# SENSOR_SCH.net
KiCad netlist of a schematic drawn in Altium Designer
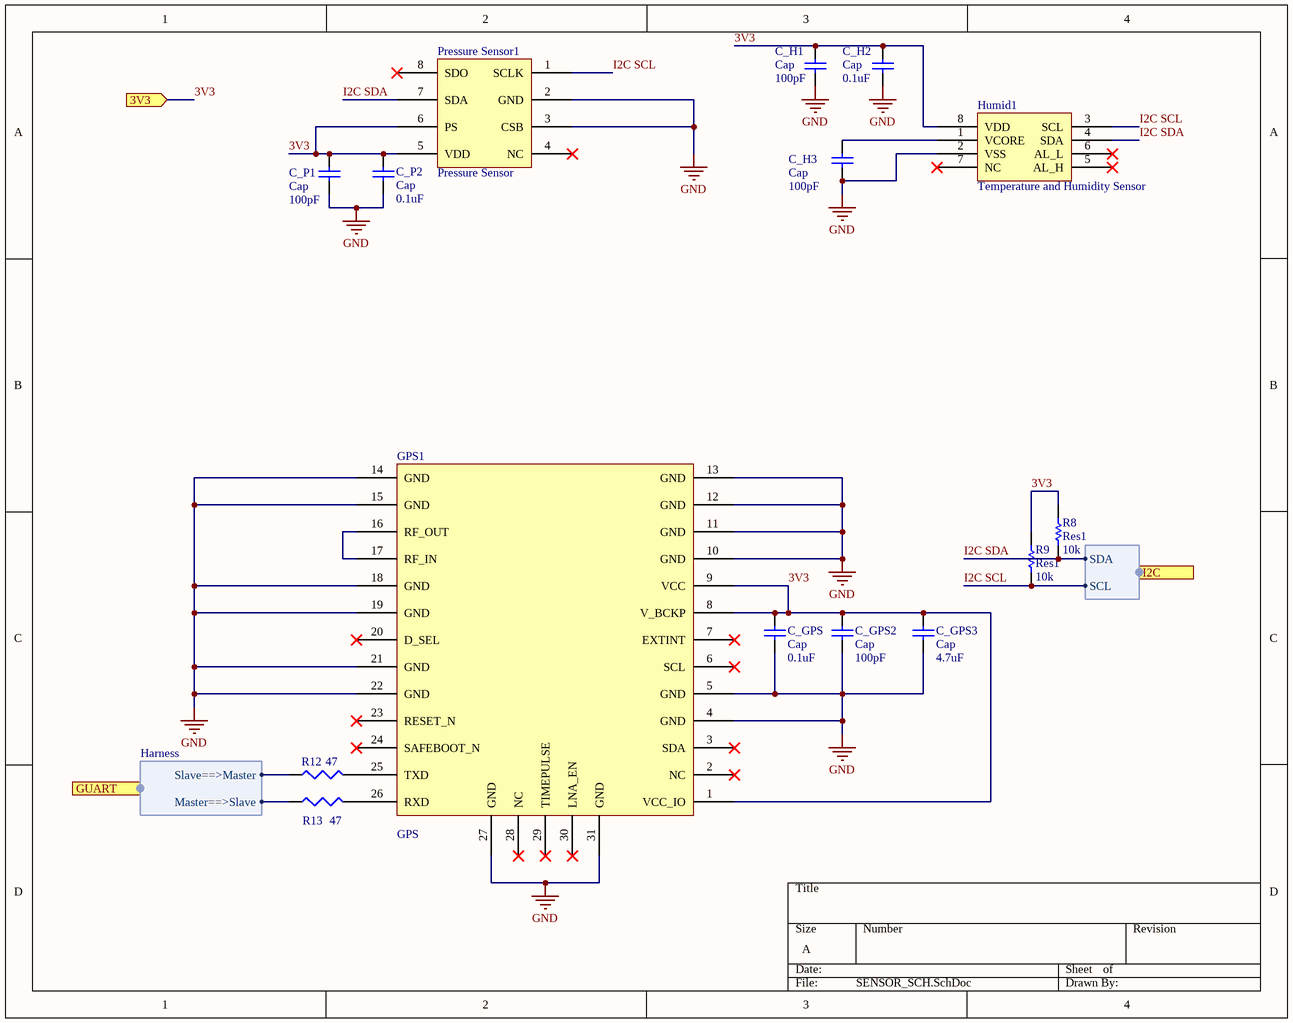
[diagram p0: SENSOR_SCH.SchDoc]

(export (version "E")
  (design (tool "Eeschema 10.0.6"))
  (components
    (comp (ref "C_GPS")
      (value "Cap")
      (footprint "1608[0603]")
      (description "Capacitor")
      (fields (field (name "ALTIUM_VALUE") "0.1uF") (field (name "PUBLISHER") "Altium Limited"))
      (libsource (lib "Miscellaneous Devices") (part "Cap"))
    )
    (comp (ref "C_GPS2")
      (value "Cap")
      (footprint "1608[0603]")
      (description "Capacitor")
      (fields (field (name "ALTIUM_VALUE") "100pF") (field (name "PUBLISHER") "Altium Limited"))
      (libsource (lib "Miscellaneous Devices") (part "Cap"))
    )
    (comp (ref "C_GPS3")
      (value "Cap")
      (footprint "1608[0603]")
      (description "Capacitor")
      (fields (field (name "ALTIUM_VALUE") "4.7uF") (field (name "PUBLISHER") "Altium Limited"))
      (libsource (lib "Miscellaneous Devices") (part "Cap"))
    )
    (comp (ref "C_H1")
      (value "Cap")
      (footprint "1608[0603]")
      (description "Capacitor")
      (fields (field (name "ALTIUM_VALUE") "100pF") (field (name "PUBLISHER") "Altium Limited"))
      (libsource (lib "Miscellaneous Devices") (part "Cap"))
    )
    (comp (ref "C_H2")
      (value "Cap")
      (footprint "1608[0603]")
      (description "Capacitor")
      (fields (field (name "ALTIUM_VALUE") "0.1uF") (field (name "PUBLISHER") "Altium Limited"))
      (libsource (lib "Miscellaneous Devices") (part "Cap"))
    )
    (comp (ref "C_H3")
      (value "Cap")
      (footprint "1608[0603]")
      (description "Capacitor")
      (fields (field (name "ALTIUM_VALUE") "100pF") (field (name "PUBLISHER") "Altium Limited"))
      (libsource (lib "Miscellaneous Devices") (part "Cap"))
    )
    (comp (ref "C_P1")
      (value "Cap")
      (footprint "1608[0603]")
      (description "Capacitor")
      (fields (field (name "ALTIUM_VALUE") "100pF") (field (name "PUBLISHER") "Altium Limited"))
      (libsource (lib "Miscellaneous Devices") (part "Cap"))
    )
    (comp (ref "C_P2")
      (value "Cap")
      (footprint "1608[0603]")
      (description "Capacitor")
      (fields (field (name "ALTIUM_VALUE") "0.1uF") (field (name "PUBLISHER") "Altium Limited"))
      (libsource (lib "Miscellaneous Devices") (part "Cap"))
    )
    (comp (ref "GPS1")
      (value "GPS")
      (footprint "CAM M8C GPS")
      (description "CAM M8C")
      (libsource (lib "ATACS_SCH_LIB") (part "GPS"))
    )
    (comp (ref "Humid1")
      (value "Temperature and Humidity Sensor")
      (footprint "Humidity Sensor")
      (description "HIH6030-021-001")
      (libsource (lib "ATACS_SCH_LIB") (part "Temperature and Humidity Sensor"))
    )
    (comp (ref "Pressure Sensor1")
      (value "Pressure Sensor")
      (footprint "Pressure Sensor")
      (description "MS580301BA01-00")
      (libsource (lib "ATACS_SCH_LIB") (part "Pressure Sensor"))
    )
    (comp (ref "R8")
      (value "Res1")
      (footprint "J1-0603")
      (description "Resistor")
      (fields (field (name "ALTIUM_VALUE") "10k") (field (name "PUBLISHER") "Altium Limited"))
      (libsource (lib "Miscellaneous Devices") (part "Res1"))
    )
    (comp (ref "R9")
      (value "Res1")
      (footprint "J1-0603")
      (description "Resistor")
      (fields (field (name "ALTIUM_VALUE") "10k") (field (name "PUBLISHER") "Altium Limited"))
      (libsource (lib "Miscellaneous Devices") (part "Res1"))
    )
    (comp (ref "R12")
      (value "47")
      (footprint "J1-0603")
      (description "Resistor")
      (fields (field (name "Comment") "Res3") (field (name "PUBLISHER") "Altium Limited"))
      (libsource (lib "Miscellaneous Devices") (part "Res3"))
    )
    (comp (ref "R13")
      (value "47")
      (footprint "J1-0603")
      (description "Resistor")
      (fields (field (name "Comment") "Res3") (field (name "PUBLISHER") "Altium Limited"))
      (libsource (lib "Miscellaneous Devices") (part "Res3"))
    )
  )
  (nets
    (net (code "3") (name "/3V3") (class "Default")
      (node (ref "C_GPS") (pin "2") (pinfunction "2_2") (pintype "passive"))
      (node (ref "C_GPS2") (pin "2") (pinfunction "2_2") (pintype "passive"))
      (node (ref "C_GPS3") (pin "2") (pinfunction "2_2") (pintype "passive"))
      (node (ref "C_H1") (pin "2") (pinfunction "2_2") (pintype "passive"))
      (node (ref "C_H2") (pin "2") (pinfunction "2_2") (pintype "passive"))
      (node (ref "C_P1") (pin "2") (pinfunction "2_2") (pintype "passive"))
      (node (ref "C_P2") (pin "2") (pinfunction "2_2") (pintype "passive"))
      (node (ref "GPS1") (pin "1") (pinfunction "VCC_IO_1") (pintype "passive"))
      (node (ref "GPS1") (pin "8") (pinfunction "V_BCKP_8") (pintype "passive"))
      (node (ref "GPS1") (pin "9") (pinfunction "VCC_9") (pintype "passive"))
      (node (ref "Humid1") (pin "8") (pinfunction "VDD_8") (pintype "passive"))
      (node (ref "Pressure Sensor1") (pin "5") (pinfunction "VDD_5") (pintype "passive"))
      (node (ref "Pressure Sensor1") (pin "6") (pinfunction "PS_6") (pintype "passive"))
      (node (ref "R8") (pin "2") (pinfunction "2_2") (pintype "passive"))
      (node (ref "R9") (pin "2") (pinfunction "2_2") (pintype "passive"))
    )
    (net (code "4") (name "/I2C SCL") (class "Default")
      (node (ref "Humid1") (pin "3") (pinfunction "SCL_3") (pintype "passive"))
      (node (ref "Pressure Sensor1") (pin "1") (pinfunction "SCLK_1") (pintype "passive"))
      (node (ref "R9") (pin "1") (pinfunction "1_1") (pintype "passive"))
    )
    (net (code "5") (name "/I2C SDA") (class "Default")
      (node (ref "Humid1") (pin "4") (pinfunction "SDA_4") (pintype "passive"))
      (node (ref "Pressure Sensor1") (pin "7") (pinfunction "SDA_7") (pintype "passive"))
      (node (ref "R8") (pin "1") (pinfunction "1_1") (pintype "passive"))
    )
    (net (code "6") (name "/Master==>Slave") (class "Default")
      (node (ref "R13") (pin "1") (pinfunction "1_1") (pintype "passive"))
    )
    (net (code "7") (name "/Slave==>Master") (class "Default")
      (node (ref "R12") (pin "1") (pinfunction "1_1") (pintype "passive"))
    )
    (net (code "10") (name "GND") (class "Default")
      (node (ref "C_GPS") (pin "1") (pinfunction "1_1") (pintype "passive"))
      (node (ref "C_GPS2") (pin "1") (pinfunction "1_1") (pintype "passive"))
      (node (ref "C_GPS3") (pin "1") (pinfunction "1_1") (pintype "passive"))
      (node (ref "C_H1") (pin "1") (pinfunction "1_1") (pintype "passive"))
      (node (ref "C_H2") (pin "1") (pinfunction "1_1") (pintype "passive"))
      (node (ref "C_H3") (pin "1") (pinfunction "1_1") (pintype "passive"))
      (node (ref "C_P1") (pin "1") (pinfunction "1_1") (pintype "passive"))
      (node (ref "C_P2") (pin "1") (pinfunction "1_1") (pintype "passive"))
      (node (ref "GPS1") (pin "10") (pinfunction "GND_10") (pintype "passive"))
      (node (ref "GPS1") (pin "11") (pinfunction "GND_11") (pintype "passive"))
      (node (ref "GPS1") (pin "12") (pinfunction "GND_12") (pintype "passive"))
      (node (ref "GPS1") (pin "13") (pinfunction "GND_13") (pintype "passive"))
      (node (ref "GPS1") (pin "14") (pinfunction "GND_14") (pintype "passive"))
      (node (ref "GPS1") (pin "15") (pinfunction "GND_15") (pintype "passive"))
      (node (ref "GPS1") (pin "18") (pinfunction "GND_18") (pintype "passive"))
      (node (ref "GPS1") (pin "19") (pinfunction "GND_19") (pintype "passive"))
      (node (ref "GPS1") (pin "21") (pinfunction "GND_21") (pintype "passive"))
      (node (ref "GPS1") (pin "22") (pinfunction "GND_22") (pintype "passive"))
      (node (ref "GPS1") (pin "27") (pinfunction "GND_27") (pintype "passive"))
      (node (ref "GPS1") (pin "31") (pinfunction "GND_31") (pintype "passive"))
      (node (ref "GPS1") (pin "4") (pinfunction "GND_4") (pintype "passive"))
      (node (ref "GPS1") (pin "5") (pinfunction "GND_5") (pintype "passive"))
      (node (ref "Humid1") (pin "2") (pinfunction "VSS_2") (pintype "passive"))
      (node (ref "Pressure Sensor1") (pin "2") (pinfunction "GND_2") (pintype "passive"))
      (node (ref "Pressure Sensor1") (pin "3") (pinfunction "CSB_3") (pintype "passive"))
    )
    (net (code "11") (name "Net-(GPS1-RF_IN)") (class "Default")
      (node (ref "GPS1") (pin "16") (pinfunction "RF_OUT_16") (pintype "passive"))
      (node (ref "GPS1") (pin "17") (pinfunction "RF_IN_17") (pintype "passive"))
    )
    (net (code "12") (name "Net-(GPS1-RXD)") (class "Default")
      (node (ref "GPS1") (pin "26") (pinfunction "RXD_26") (pintype "passive"))
      (node (ref "R13") (pin "2") (pinfunction "2_2") (pintype "passive"))
    )
    (net (code "13") (name "Net-(GPS1-TXD)") (class "Default")
      (node (ref "GPS1") (pin "25") (pinfunction "TXD_25") (pintype "passive"))
      (node (ref "R12") (pin "2") (pinfunction "2_2") (pintype "passive"))
    )
    (net (code "14") (name "Net-(Humid1-VCORE)") (class "Default")
      (node (ref "C_H3") (pin "2") (pinfunction "2_2") (pintype "passive"))
      (node (ref "Humid1") (pin "1") (pinfunction "VCORE_1") (pintype "passive"))
    )
    (net (code "15") (name "unconnected-(GPS1-D_SEL-Pad20)") (class "Default")
      (node (ref "GPS1") (pin "20") (pinfunction "D_SEL_20") (pintype "passive+no_connect"))
    )
    (net (code "16") (name "unconnected-(GPS1-EXTINT-Pad7)") (class "Default")
      (node (ref "GPS1") (pin "7") (pinfunction "EXTINT_7") (pintype "passive+no_connect"))
    )
    (net (code "17") (name "unconnected-(GPS1-LNA_EN-Pad30)") (class "Default")
      (node (ref "GPS1") (pin "30") (pinfunction "LNA_EN_30") (pintype "passive+no_connect"))
    )
    (net (code "18") (name "unconnected-(GPS1-NC-Pad2)") (class "Default")
      (node (ref "GPS1") (pin "2") (pinfunction "NC_2") (pintype "passive+no_connect"))
    )
    (net (code "19") (name "unconnected-(GPS1-NC-Pad28)") (class "Default")
      (node (ref "GPS1") (pin "28") (pinfunction "NC_28") (pintype "passive+no_connect"))
    )
    (net (code "20") (name "unconnected-(GPS1-RESET_N-Pad23)") (class "Default")
      (node (ref "GPS1") (pin "23") (pinfunction "RESET_N_23") (pintype "passive+no_connect"))
    )
    (net (code "21") (name "unconnected-(GPS1-SAFEBOOT_N-Pad24)") (class "Default")
      (node (ref "GPS1") (pin "24") (pinfunction "SAFEBOOT_N_24") (pintype "passive+no_connect"))
    )
    (net (code "22") (name "unconnected-(GPS1-SCL-Pad6)") (class "Default")
      (node (ref "GPS1") (pin "6") (pinfunction "SCL_6") (pintype "passive+no_connect"))
    )
    (net (code "23") (name "unconnected-(GPS1-SDA-Pad3)") (class "Default")
      (node (ref "GPS1") (pin "3") (pinfunction "SDA_3") (pintype "passive+no_connect"))
    )
    (net (code "24") (name "unconnected-(GPS1-TIMEPULSE-Pad29)") (class "Default")
      (node (ref "GPS1") (pin "29") (pinfunction "TIMEPULSE_29") (pintype "passive+no_connect"))
    )
    (net (code "25") (name "unconnected-(Humid1-AL_H-Pad5)") (class "Default")
      (node (ref "Humid1") (pin "5") (pinfunction "AL_H_5") (pintype "passive+no_connect"))
    )
    (net (code "26") (name "unconnected-(Humid1-AL_L-Pad6)") (class "Default")
      (node (ref "Humid1") (pin "6") (pinfunction "AL_L_6") (pintype "passive+no_connect"))
    )
    (net (code "27") (name "unconnected-(Humid1-NC-Pad7)") (class "Default")
      (node (ref "Humid1") (pin "7") (pinfunction "NC_7") (pintype "passive+no_connect"))
    )
    (net (code "28") (name "unconnected-(Pressure Sensor1-NC-Pad4)") (class "Default")
      (node (ref "Pressure Sensor1") (pin "4") (pinfunction "NC_4") (pintype "passive+no_connect"))
    )
    (net (code "29") (name "unconnected-(Pressure Sensor1-SDO-Pad8)") (class "Default")
      (node (ref "Pressure Sensor1") (pin "8") (pinfunction "SDO_8") (pintype "passive+no_connect"))
    )
  )
)
